# Microphone_PreAmp.net
KiCad netlist of a schematic drawn in Altium Designer
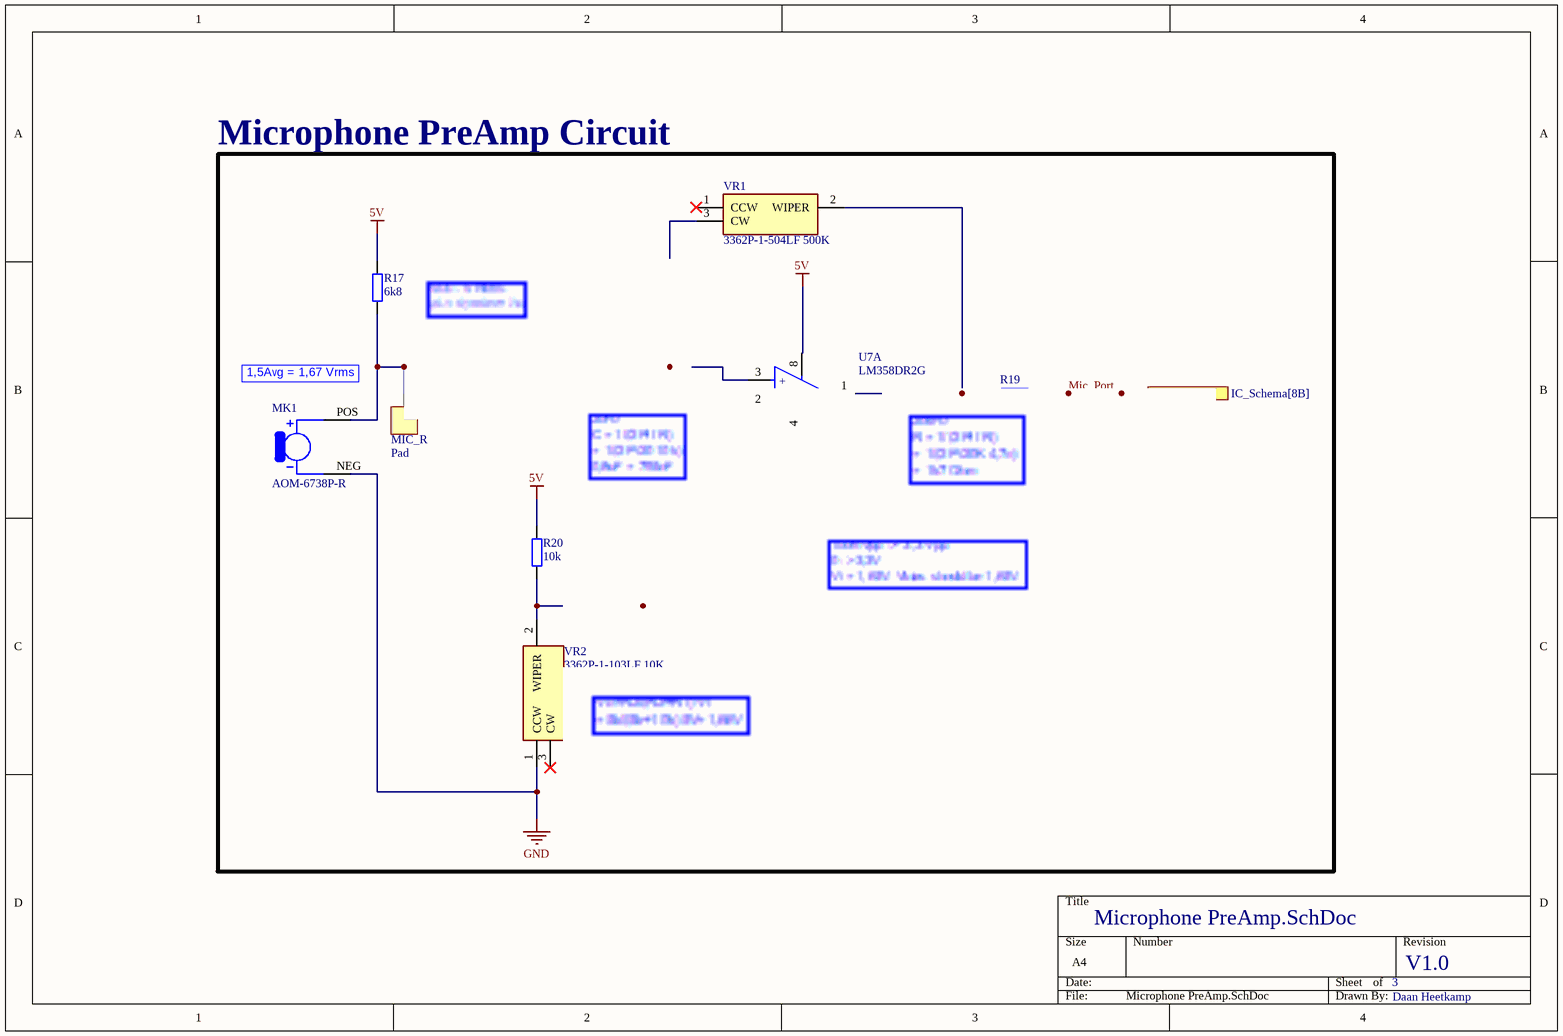
[diagram p0: Microphone PreAmp.SchDoc]

(export (version "E")
  (design (tool "Eeschema 10.0.6"))
  (components
    (comp (ref "Bias")
      (value "Pad")
      (footprint "PAD_SQ_2MM")
      (description "Test Point Square 2mm")
      (libsource (lib "Schem_Lib_DaanHeetkamp.") (part "PAD_SQ_2MM"))
    )
    (comp (ref "C13")
      (value "4u7")
      (footprint "CAP_0603")
      (description "Capacitor SMD 0603 50V")
      (libsource (lib "Schem_Lib_DaanHeetkamp") (part "CAP_0603_50V"))
    )
    (comp (ref "C14")
      (value "4n7")
      (footprint "CAP_0603")
      (description "Capacitor SMD 0603 50V")
      (libsource (lib "Schem_Lib_DaanHeetkamp") (part "CAP_0603_50V"))
    )
    (comp (ref "MIC_O")
      (value "Pad")
      (footprint "PAD_SQ_2MM")
      (description "Test Point Square 2mm")
      (libsource (lib "") (part "PAD_SQ_2MM_1"))
    )
    (comp (ref "MIC_R")
      (value "Pad")
      (footprint "PAD_SQ_2MM")
      (description "Test Point Square 2mm")
      (libsource (lib "") (part "PAD_SQ_2MM_1"))
    )
    (comp (ref "MK1")
      (value "AOM-6738P-R")
      (footprint "PCB_Lib_DaanHeetkamp:MIC_AOM-6738P-R")
      (description "30Hz ~ 15kHz Analog Microphone Electret Condenser 1.5V ~ 10V Omnidirectional _-38dB Â±3dB_ PC Pins")
      (fields (field (name "MF") "PUI"))
      (libsource (lib "Schem_Lib_DaanHeetkamp.") (part "AOM-6738P-R"))
    )
    (comp (ref "R17")
      (value "6k8")
      (footprint "RES_1206")
      (description "Resistor SMD 1206")
      (libsource (lib "Schem_Lib_DaanHeetkamp.") (part "RES_1206"))
    )
    (comp (ref "R18")
      (value "10k")
      (footprint "RES_1206")
      (description "Resistor SMD 1206")
      (libsource (lib "Schem_Lib_DaanHeetkamp.") (part "RES_1206"))
    )
    (comp (ref "R19")
      (value "1k7")
      (footprint "RES_1206")
      (description "Resistor SMD 1206")
      (libsource (lib "Schem_Lib_DaanHeetkamp.") (part "RES_1206"))
    )
    (comp (ref "R20")
      (value "10k")
      (footprint "RES_1206")
      (description "Resistor SMD 1206")
      (libsource (lib "Schem_Lib_DaanHeetkamp.") (part "RES_1206"))
    )
    (comp (ref "U7")
      (value "LM358DR2G")
      (footprint "FP-751-07-IPC_C")
      (description "IC OPAMP GP 2 CIRCUIT 8SOIC")
      (libsource (lib "Altium Content Vault") (part "992a6607d1d88c80ee6b45e5ba6cb1b"))
    )
    (comp (ref "VR1")
      (value "3362P-1-504LF 500K")
      (footprint "PCB_Lib_DaanHeetkamp:3362P1504LF")
      (description "Variable Resistor")
      (fields
        (field (name "MANUFACTURER_PART_NUMBER") "3362P-1-504LF")
        (field (name "MOUSER PART NUMBER") "652-3362P-1-504LF")
      )
      (libsource (lib "") (part "3362P-1-504LF_1"))
    )
    (comp (ref "VR2")
      (value "3362P-1-103LF 10K")
      (footprint "PCB_Lib_DaanHeetkamp:3362P1504LF")
      (description "Variable Resistor")
      (fields
        (field (name "MANUFACTURER_PART_NUMBER") "3362P-1-504LF")
        (field (name "MOUSER PART NUMBER") "652-3362P-1-504LF")
      )
      (libsource (lib "Schem_Lib_DaanHeetkamp.") (part "3362P-1-504LF"))
    )
  )
  (nets
    (net (code "1") (name "/Mic_Port") (class "Default")
      (node (ref "C14") (pin "1") (pinfunction "1_1") (pintype "passive"))
      (node (ref "MIC_O") (pin "1") (pinfunction "1_1") (pintype "passive"))
      (node (ref "R19") (pin "1") (pinfunction "1_1") (pintype "passive"))
    )
    (net (code "2") (name "5V") (class "Default")
      (node (ref "R17") (pin "1") (pinfunction "1_1") (pintype "passive"))
      (node (ref "R20") (pin "2") (pinfunction "2_2") (pintype "passive"))
      (node (ref "U7") (pin "8") (pinfunction "VCC_8") (pintype "power_in"))
    )
    (net (code "3") (name "GND") (class "Default")
      (node (ref "C14") (pin "2") (pinfunction "2_2") (pintype "passive"))
      (node (ref "MK1") (pin "NEG") (pinfunction "NEG_NEG") (pintype "passive"))
      (node (ref "U7") (pin "4") (pinfunction "VEE/GND_4") (pintype "power_in"))
      (node (ref "VR2") (pin "1") (pinfunction "CCW_1") (pintype "passive"))
    )
    (net (code "4") (name "Net-(C13-Pad1)") (class "Default")
      (node (ref "C13") (pin "1") (pinfunction "1_1") (pintype "passive"))
      (node (ref "R18") (pin "2") (pinfunction "2_2") (pintype "passive"))
    )
    (net (code "5") (name "Net-(C13-Pad2)") (class "Default")
      (node (ref "C13") (pin "2") (pinfunction "2_2") (pintype "passive"))
      (node (ref "MIC_R") (pin "1") (pinfunction "1_1") (pintype "passive"))
      (node (ref "MK1") (pin "POS") (pinfunction "POS_POS") (pintype "passive"))
      (node (ref "R17") (pin "2") (pinfunction "2_2") (pintype "passive"))
    )
    (net (code "6") (name "Net-(U7A-INPUT_A+)") (class "Default")
      (node (ref "R18") (pin "1") (pinfunction "1_1") (pintype "passive"))
      (node (ref "U7") (pin "3") (pinfunction "INPUT_A+_3") (pintype "tri_state"))
      (node (ref "VR1") (pin "3") (pinfunction "CW_3") (pintype "passive"))
    )
    (net (code "7") (name "Net-(U7A-INPUT_A-)") (class "Default")
      (node (ref "Bias") (pin "1") (pinfunction "1_1") (pintype "passive"))
      (node (ref "R20") (pin "1") (pinfunction "1_1") (pintype "passive"))
      (node (ref "U7") (pin "2") (pinfunction "INPUT_A-_2") (pintype "tri_state"))
      (node (ref "VR2") (pin "2") (pinfunction "WIPER_2") (pintype "passive"))
    )
    (net (code "8") (name "Net-(U7A-OUTPUT_A)") (class "Default")
      (node (ref "R19") (pin "2") (pinfunction "2_2") (pintype "passive"))
      (node (ref "U7") (pin "1") (pinfunction "OUTPUT_A_1") (pintype "output"))
      (node (ref "VR1") (pin "2") (pinfunction "WIPER_2") (pintype "passive"))
    )
    (net (code "9") (name "unconnected-(VR1-CCW-Pad1)") (class "Default")
      (node (ref "VR1") (pin "1") (pinfunction "CCW_1") (pintype "passive+no_connect"))
    )
    (net (code "10") (name "unconnected-(VR2-CW-Pad3)") (class "Default")
      (node (ref "VR2") (pin "3") (pinfunction "CW_3") (pintype "passive+no_connect"))
    )
  )
)
